# Arduino_Shield_RC_Controller_v2.net
KiCad netlist of a schematic drawn in EAGLE
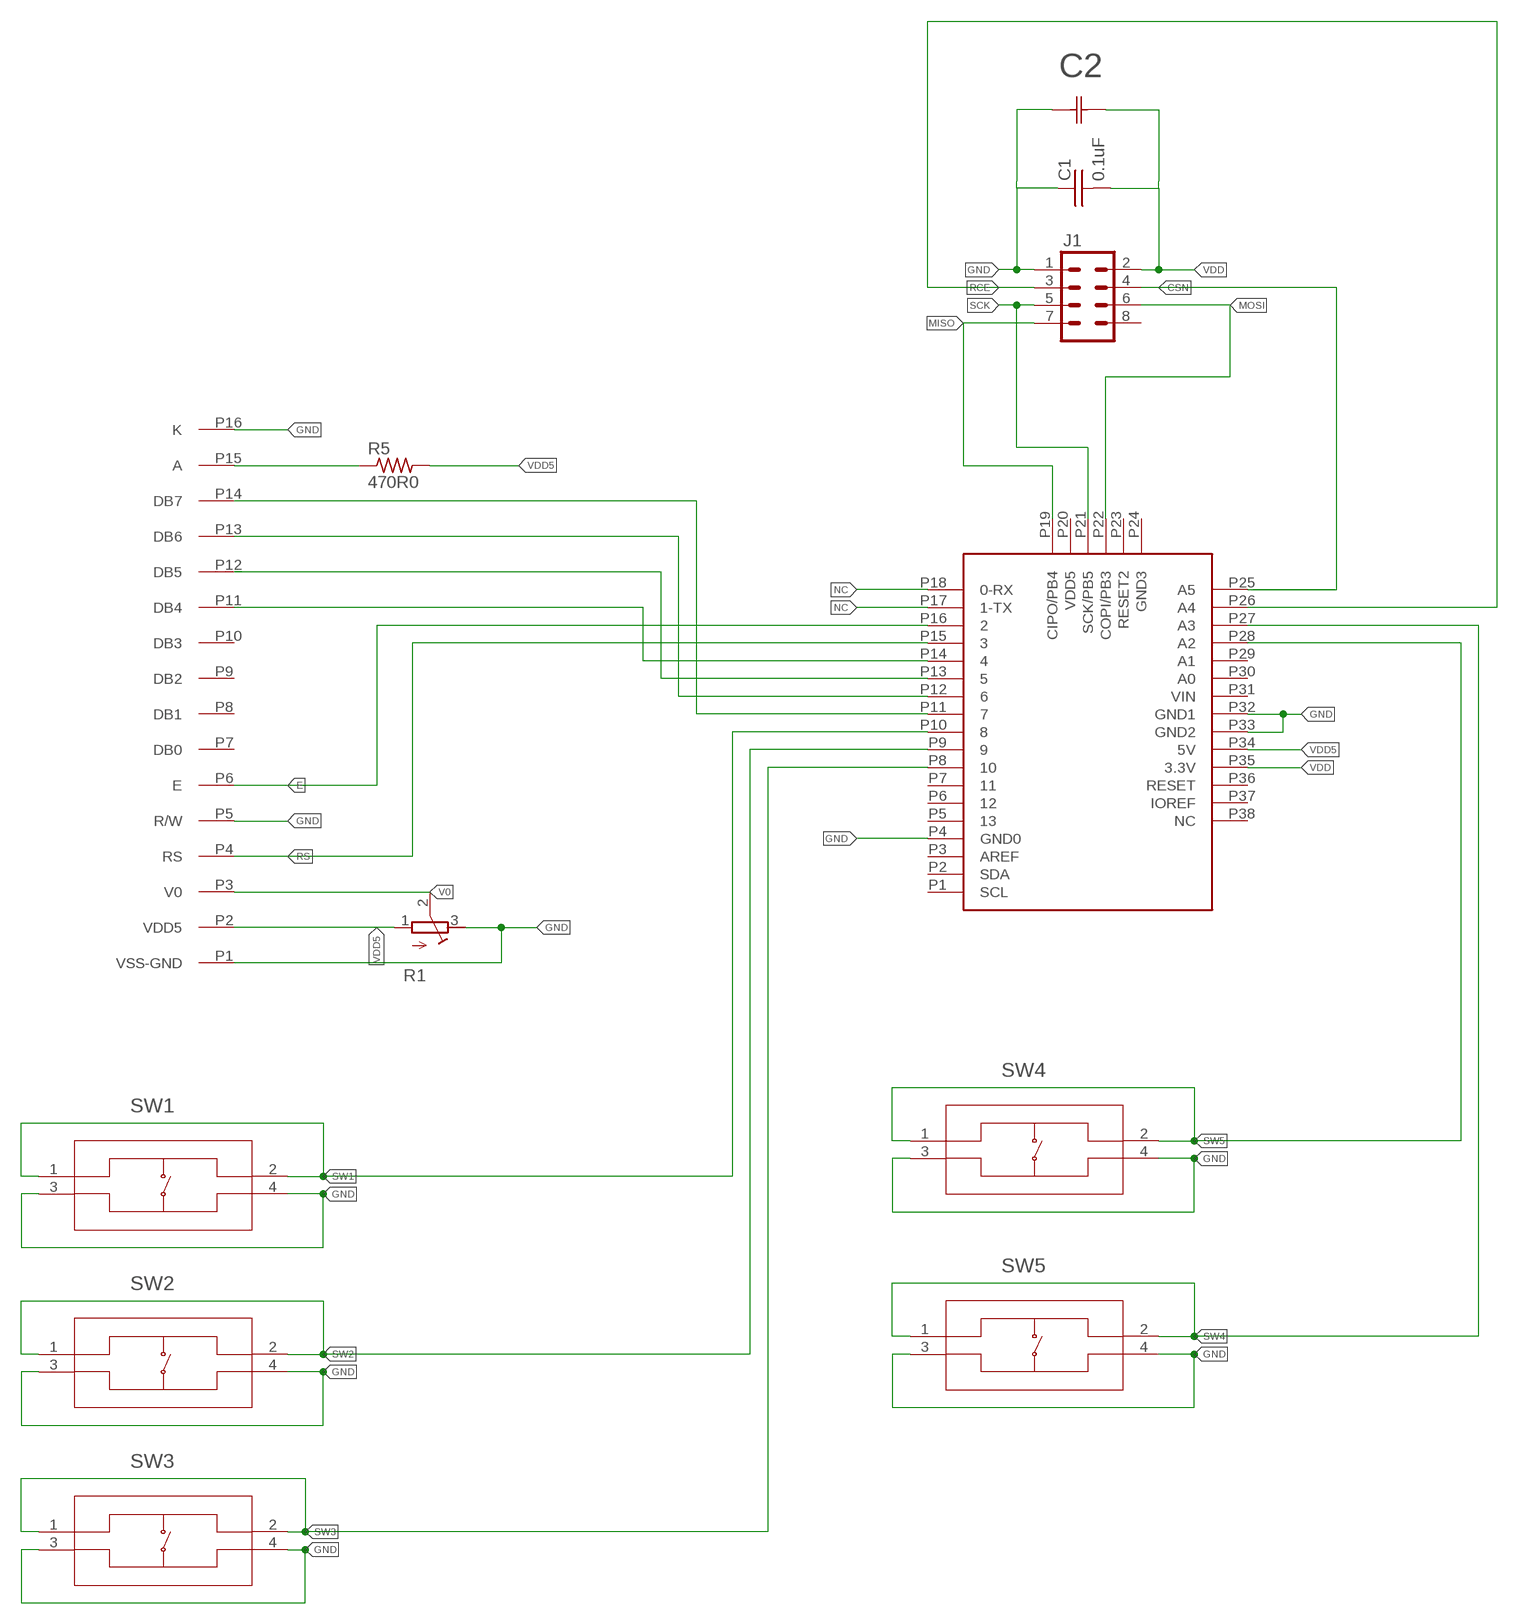
[diagram p0: schematic, sheet 1]

(export (version "E")
  (design (tool "Eeschema 10.0.6"))
  (components
    (comp (ref "AR1")
      (value "ARDUINO_R3")
      (footprint "eagle-import:ARDUINO_R3")
      (libsource (lib "eagle-import") (part "ARDUINO_R3"))
    )
    (comp (ref "C1")
      (value "0.1uF")
      (footprint "eagle-import:0402")
      (fields (field (name "PARTNO") "CL05F104ZO5NNNC"))
      (libsource (lib "eagle-import") (part "C_0402_0.1UF"))
    )
    (comp (ref "C2")
      (value "CAP_470UF_RAD_TH")
      (footprint "eagle-import:CAP_YX_10X16_RUB")
      (fields
        (field (name "MANUFACTURER_PART_NUMBER") "35ZLH470MEFC10X16")
        (field (name "COPYRIGHT") "Copyright (C) 2023 Ultra Librarian. All rights reserved.")
      )
      (libsource (lib "eagle-import") (part "CAP_470UF_RAD_TH"))
    )
    (comp (ref "J1")
      (value "CONN_04X2")
      (footprint "eagle-import:2X4")
      (libsource (lib "eagle-import") (part "CONN_04X2"))
    )
    (comp (ref "LCD1")
      (value "ADM1602K")
      (footprint "eagle-import:ADM1602K")
      (libsource (lib "eagle-import") (part "ADM1602K"))
    )
    (comp (ref "R1")
      (value "R-TRIMM3103")
      (footprint "eagle-import:RTRIM3103")
      (libsource (lib "eagle-import") (part "R-TRIMM3103"))
    )
    (comp (ref "R5")
      (value "470R0")
      (footprint "eagle-import:0402")
      (fields (field (name "PARTNO") "RMCF0402JT470R"))
      (libsource (lib "eagle-import") (part "R_0402_470R0"))
    )
    (comp (ref "SW1")
      (value "PTS810SJG250SMTRLFS")
      (footprint "eagle-import:PTS810")
      (fields (field (name "COPYRIGHT") "Copyright (C) 2018 Accelerated Designs. All rights reserved"))
      (libsource (lib "eagle-import") (part "PTS810SJG250SMTRLFS"))
    )
    (comp (ref "SW2")
      (value "PTS810SJG250SMTRLFS")
      (footprint "eagle-import:PTS810")
      (fields (field (name "COPYRIGHT") "Copyright (C) 2018 Accelerated Designs. All rights reserved"))
      (libsource (lib "eagle-import") (part "PTS810SJG250SMTRLFS"))
    )
    (comp (ref "SW3")
      (value "PTS810SJG250SMTRLFS")
      (footprint "eagle-import:PTS810")
      (fields (field (name "COPYRIGHT") "Copyright (C) 2018 Accelerated Designs. All rights reserved"))
      (libsource (lib "eagle-import") (part "PTS810SJG250SMTRLFS"))
    )
    (comp (ref "SW4")
      (value "PTS810SJG250SMTRLFS")
      (footprint "eagle-import:PTS810")
      (fields (field (name "COPYRIGHT") "Copyright (C) 2018 Accelerated Designs. All rights reserved"))
      (libsource (lib "eagle-import") (part "PTS810SJG250SMTRLFS"))
    )
    (comp (ref "SW5")
      (value "PTS810SJG250SMTRLFS")
      (footprint "eagle-import:PTS810")
      (fields (field (name "COPYRIGHT") "Copyright (C) 2018 Accelerated Designs. All rights reserved"))
      (libsource (lib "eagle-import") (part "PTS810SJG250SMTRLFS"))
    )
  )
  (nets
    (net (code "1") (name "CSN") (class "Default")
      (node (ref "AR1") (pin "P25") (pinfunction "A5_P25") (pintype "bidirectional"))
      (node (ref "J1") (pin "4") (pinfunction "4_4") (pintype "passive"))
    )
    (net (code "2") (name "E") (class "Default")
      (node (ref "AR1") (pin "P16") (pinfunction "2_P16") (pintype "bidirectional"))
      (node (ref "LCD1") (pin "P6") (pinfunction "E_P6") (pintype "bidirectional"))
    )
    (net (code "3") (name "GND") (class "Default")
      (node (ref "AR1") (pin "P32") (pinfunction "GND1_P32") (pintype "bidirectional"))
      (node (ref "AR1") (pin "P33") (pinfunction "GND2_P33") (pintype "bidirectional"))
      (node (ref "AR1") (pin "P4") (pinfunction "GND0_P4") (pintype "bidirectional"))
      (node (ref "C1") (pin "P$1") (pinfunction "1_P$1") (pintype "passive"))
      (node (ref "C2") (pin "1") (pinfunction "1_1") (pintype "passive"))
      (node (ref "J1") (pin "1") (pinfunction "1_1") (pintype "passive"))
      (node (ref "LCD1") (pin "P1") (pinfunction "VSS-GND_P1") (pintype "bidirectional"))
      (node (ref "LCD1") (pin "P16") (pinfunction "K_P16") (pintype "bidirectional"))
      (node (ref "LCD1") (pin "P5") (pinfunction "R/W_P5") (pintype "bidirectional"))
      (node (ref "R1") (pin "3") (pinfunction "E_3") (pintype "passive"))
      (node (ref "SW1") (pin "3") (pinfunction "3_3") (pintype "passive"))
      (node (ref "SW1") (pin "4") (pinfunction "4_4") (pintype "passive"))
      (node (ref "SW2") (pin "3") (pinfunction "3_3") (pintype "passive"))
      (node (ref "SW2") (pin "4") (pinfunction "4_4") (pintype "passive"))
      (node (ref "SW3") (pin "3") (pinfunction "3_3") (pintype "passive"))
      (node (ref "SW3") (pin "4") (pinfunction "4_4") (pintype "passive"))
      (node (ref "SW4") (pin "3") (pinfunction "3_3") (pintype "passive"))
      (node (ref "SW4") (pin "4") (pinfunction "4_4") (pintype "passive"))
      (node (ref "SW5") (pin "3") (pinfunction "3_3") (pintype "passive"))
      (node (ref "SW5") (pin "4") (pinfunction "4_4") (pintype "passive"))
    )
    (net (code "4") (name "MISO") (class "Default")
      (node (ref "AR1") (pin "P19") (pinfunction "CIPO/PB4_P19") (pintype "bidirectional"))
      (node (ref "J1") (pin "7") (pinfunction "7_7") (pintype "passive"))
    )
    (net (code "5") (name "MOSI") (class "Default")
      (node (ref "AR1") (pin "P22") (pinfunction "COPI/PB3_P22") (pintype "bidirectional"))
      (node (ref "J1") (pin "6") (pinfunction "6_6") (pintype "passive"))
    )
    (net (code "6") (name "NC") (class "Default")
      (node (ref "AR1") (pin "P17") (pinfunction "1-TX_P17") (pintype "bidirectional"))
      (node (ref "AR1") (pin "P18") (pinfunction "0-RX_P18") (pintype "bidirectional"))
    )
    (net (code "7") (name "Net-(AR1-4)") (class "Default")
      (node (ref "AR1") (pin "P14") (pinfunction "4_P14") (pintype "bidirectional"))
      (node (ref "LCD1") (pin "P11") (pinfunction "DB4_P11") (pintype "bidirectional"))
    )
    (net (code "8") (name "Net-(AR1-5)") (class "Default")
      (node (ref "AR1") (pin "P13") (pinfunction "5_P13") (pintype "bidirectional"))
      (node (ref "LCD1") (pin "P12") (pinfunction "DB5_P12") (pintype "bidirectional"))
    )
    (net (code "9") (name "Net-(AR1-6)") (class "Default")
      (node (ref "AR1") (pin "P12") (pinfunction "6_P12") (pintype "bidirectional"))
      (node (ref "LCD1") (pin "P13") (pinfunction "DB6_P13") (pintype "bidirectional"))
    )
    (net (code "10") (name "Net-(AR1-7)") (class "Default")
      (node (ref "AR1") (pin "P11") (pinfunction "7_P11") (pintype "bidirectional"))
      (node (ref "LCD1") (pin "P14") (pinfunction "DB7_P14") (pintype "bidirectional"))
    )
    (net (code "11") (name "Net-(LCD1-A)") (class "Default")
      (node (ref "LCD1") (pin "P15") (pinfunction "A_P15") (pintype "bidirectional"))
      (node (ref "R5") (pin "P$1") (pinfunction "1_P$1") (pintype "passive"))
    )
    (net (code "12") (name "RCE") (class "Default")
      (node (ref "AR1") (pin "P26") (pinfunction "A4_P26") (pintype "bidirectional"))
      (node (ref "J1") (pin "3") (pinfunction "3_3") (pintype "passive"))
    )
    (net (code "13") (name "RS") (class "Default")
      (node (ref "AR1") (pin "P15") (pinfunction "3_P15") (pintype "bidirectional"))
      (node (ref "LCD1") (pin "P4") (pinfunction "RS_P4") (pintype "bidirectional"))
    )
    (net (code "14") (name "SCK") (class "Default")
      (node (ref "AR1") (pin "P21") (pinfunction "SCK/PB5_P21") (pintype "bidirectional"))
      (node (ref "J1") (pin "5") (pinfunction "5_5") (pintype "passive"))
    )
    (net (code "15") (name "SW1") (class "Default")
      (node (ref "AR1") (pin "P10") (pinfunction "8_P10") (pintype "bidirectional"))
      (node (ref "SW1") (pin "1") (pinfunction "1_1") (pintype "passive"))
      (node (ref "SW1") (pin "2") (pinfunction "2_2") (pintype "passive"))
    )
    (net (code "16") (name "SW2") (class "Default")
      (node (ref "AR1") (pin "P9") (pinfunction "9_P9") (pintype "bidirectional"))
      (node (ref "SW2") (pin "1") (pinfunction "1_1") (pintype "passive"))
      (node (ref "SW2") (pin "2") (pinfunction "2_2") (pintype "passive"))
    )
    (net (code "17") (name "SW3") (class "Default")
      (node (ref "AR1") (pin "P8") (pinfunction "10_P8") (pintype "bidirectional"))
      (node (ref "SW3") (pin "1") (pinfunction "1_1") (pintype "passive"))
      (node (ref "SW3") (pin "2") (pinfunction "2_2") (pintype "passive"))
    )
    (net (code "18") (name "SW4") (class "Default")
      (node (ref "AR1") (pin "P27") (pinfunction "A3_P27") (pintype "bidirectional"))
      (node (ref "SW5") (pin "1") (pinfunction "1_1") (pintype "passive"))
      (node (ref "SW5") (pin "2") (pinfunction "2_2") (pintype "passive"))
    )
    (net (code "19") (name "SW5") (class "Default")
      (node (ref "AR1") (pin "P28") (pinfunction "A2_P28") (pintype "bidirectional"))
      (node (ref "SW4") (pin "1") (pinfunction "1_1") (pintype "passive"))
      (node (ref "SW4") (pin "2") (pinfunction "2_2") (pintype "passive"))
    )
    (net (code "20") (name "V0") (class "Default")
      (node (ref "LCD1") (pin "P3") (pinfunction "V0_P3") (pintype "bidirectional"))
      (node (ref "R1") (pin "2") (pinfunction "S_2") (pintype "passive"))
    )
    (net (code "21") (name "VDD") (class "Default")
      (node (ref "AR1") (pin "P35") (pinfunction "3.3V_P35") (pintype "bidirectional"))
      (node (ref "C1") (pin "P$2") (pinfunction "2_P$2") (pintype "passive"))
      (node (ref "C2") (pin "2") (pinfunction "2_2") (pintype "passive"))
      (node (ref "J1") (pin "2") (pinfunction "2_2") (pintype "passive"))
    )
    (net (code "22") (name "VDD5") (class "Default")
      (node (ref "AR1") (pin "P34") (pinfunction "5V_P34") (pintype "bidirectional"))
      (node (ref "LCD1") (pin "P2") (pinfunction "VDD5_P2") (pintype "bidirectional"))
      (node (ref "R1") (pin "1") (pinfunction "A_1") (pintype "passive"))
      (node (ref "R5") (pin "P$2") (pinfunction "2_P$2") (pintype "passive"))
    )
    (net (code "23") (name "unconnected-(AR1-11-PadP7)") (class "Default")
      (node (ref "AR1") (pin "P7") (pinfunction "11_P7") (pintype "bidirectional"))
    )
    (net (code "24") (name "unconnected-(AR1-12-PadP6)") (class "Default")
      (node (ref "AR1") (pin "P6") (pinfunction "12_P6") (pintype "bidirectional"))
    )
    (net (code "25") (name "unconnected-(AR1-13-PadP5)") (class "Default")
      (node (ref "AR1") (pin "P5") (pinfunction "13_P5") (pintype "bidirectional"))
    )
    (net (code "26") (name "unconnected-(AR1-A0-PadP30)") (class "Default")
      (node (ref "AR1") (pin "P30") (pinfunction "A0_P30") (pintype "bidirectional"))
    )
    (net (code "27") (name "unconnected-(AR1-A1-PadP29)") (class "Default")
      (node (ref "AR1") (pin "P29") (pinfunction "A1_P29") (pintype "bidirectional"))
    )
    (net (code "28") (name "unconnected-(AR1-AREF-PadP3)") (class "Default")
      (node (ref "AR1") (pin "P3") (pinfunction "AREF_P3") (pintype "bidirectional"))
    )
    (net (code "29") (name "unconnected-(AR1-GND3-PadP24)") (class "Default")
      (node (ref "AR1") (pin "P24") (pinfunction "GND3_P24") (pintype "bidirectional"))
    )
    (net (code "30") (name "unconnected-(AR1-IOREF-PadP37)") (class "Default")
      (node (ref "AR1") (pin "P37") (pinfunction "IOREF_P37") (pintype "bidirectional"))
    )
    (net (code "31") (name "unconnected-(AR1-NC-PadP38)") (class "Default")
      (node (ref "AR1") (pin "P38") (pinfunction "NC_P38") (pintype "bidirectional"))
    )
    (net (code "32") (name "unconnected-(AR1-RESET-PadP36)") (class "Default")
      (node (ref "AR1") (pin "P36") (pinfunction "RESET_P36") (pintype "bidirectional"))
    )
    (net (code "33") (name "unconnected-(AR1-RESET2-PadP23)") (class "Default")
      (node (ref "AR1") (pin "P23") (pinfunction "RESET2_P23") (pintype "bidirectional"))
    )
    (net (code "34") (name "unconnected-(AR1-SCL-PadP1)") (class "Default")
      (node (ref "AR1") (pin "P1") (pinfunction "SCL_P1") (pintype "bidirectional"))
    )
    (net (code "35") (name "unconnected-(AR1-SDA-PadP2)") (class "Default")
      (node (ref "AR1") (pin "P2") (pinfunction "SDA_P2") (pintype "bidirectional"))
    )
    (net (code "36") (name "unconnected-(AR1-VDD5-PadP20)") (class "Default")
      (node (ref "AR1") (pin "P20") (pinfunction "VDD5_P20") (pintype "bidirectional"))
    )
    (net (code "37") (name "unconnected-(AR1-VIN-PadP31)") (class "Default")
      (node (ref "AR1") (pin "P31") (pinfunction "VIN_P31") (pintype "bidirectional"))
    )
    (net (code "38") (name "unconnected-(J1-Pad8)") (class "Default")
      (node (ref "J1") (pin "8") (pinfunction "8_8") (pintype "passive"))
    )
    (net (code "39") (name "unconnected-(LCD1-DB0-PadP7)") (class "Default")
      (node (ref "LCD1") (pin "P7") (pinfunction "DB0_P7") (pintype "bidirectional"))
    )
    (net (code "40") (name "unconnected-(LCD1-DB1-PadP8)") (class "Default")
      (node (ref "LCD1") (pin "P8") (pinfunction "DB1_P8") (pintype "bidirectional"))
    )
    (net (code "41") (name "unconnected-(LCD1-DB2-PadP9)") (class "Default")
      (node (ref "LCD1") (pin "P9") (pinfunction "DB2_P9") (pintype "bidirectional"))
    )
    (net (code "42") (name "unconnected-(LCD1-DB3-PadP10)") (class "Default")
      (node (ref "LCD1") (pin "P10") (pinfunction "DB3_P10") (pintype "bidirectional"))
    )
  )
)
